# nfc-epd-eink.net
KiCad netlist of a schematic drawn in Altium Designer
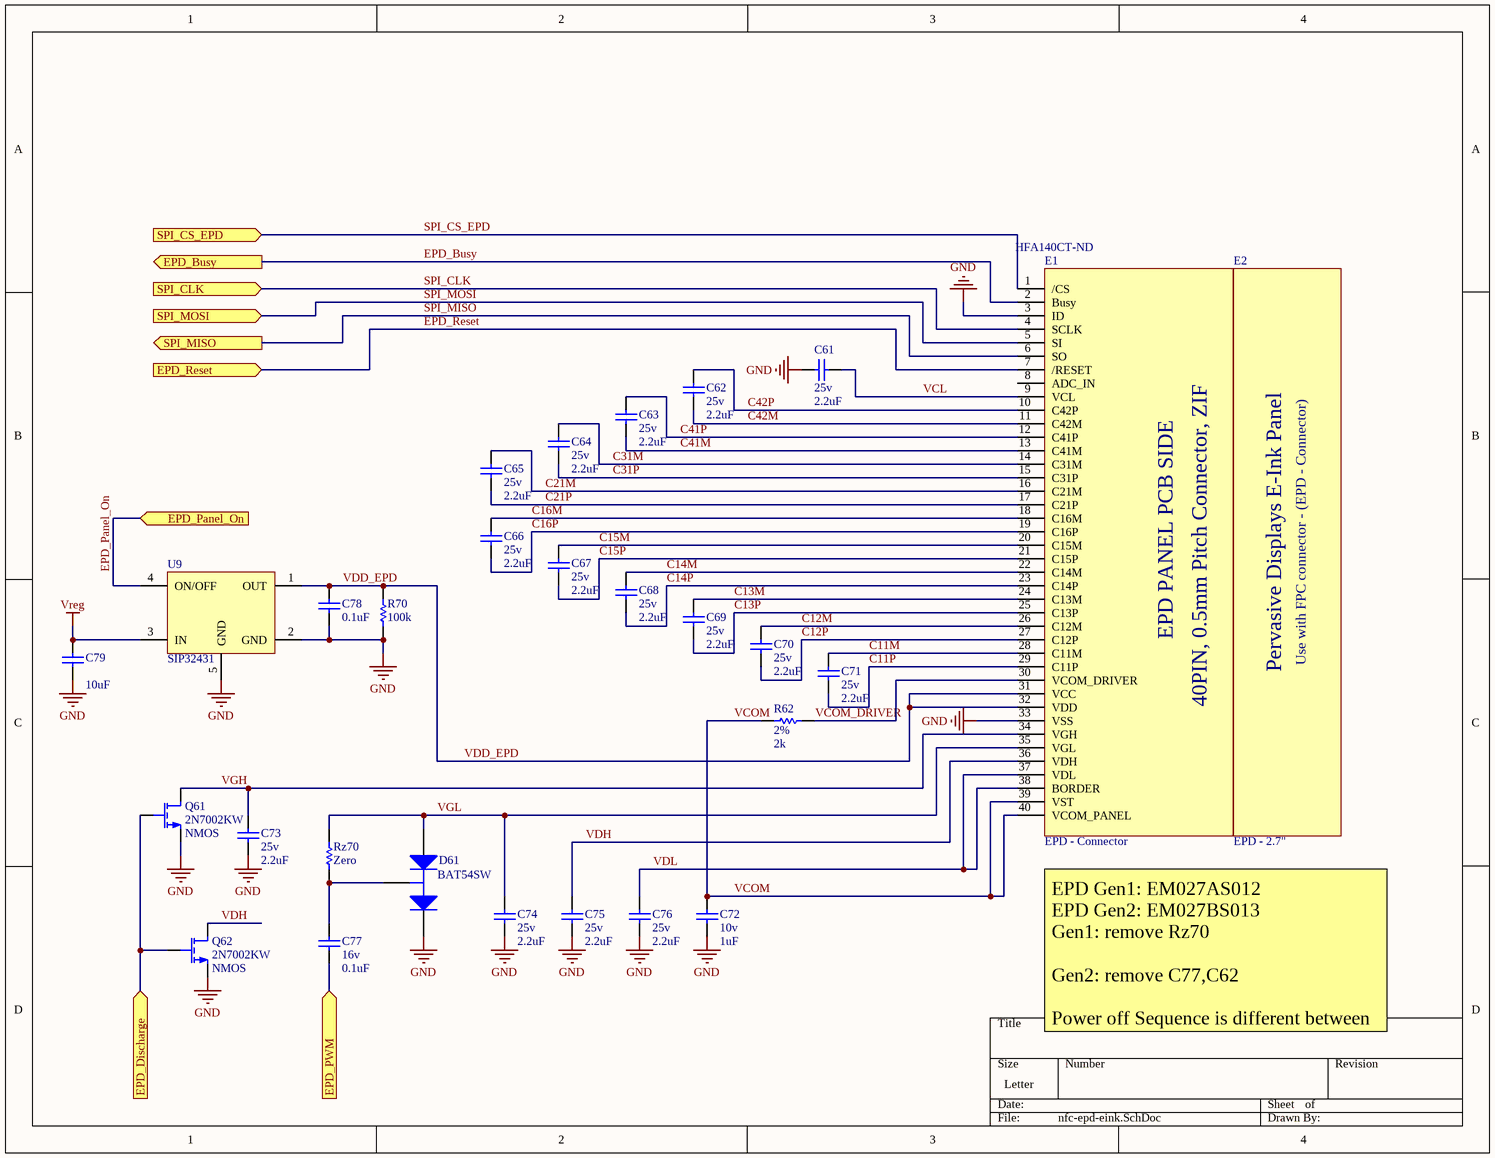
[diagram p0: nfc-epd-eink.SchDoc]

(export (version "E")
  (design (tool "Eeschema 10.0.6"))
  (components
    (comp (ref "C61")
      (value "2.2uF")
      (footprint "0402")
      (description "Ceramic Capacitor (Surface Mount)")
      (fields
        (field (name "MANUFACTURER") "Generic Ceramic Chip Cap (TBD)")
        (field (name "RATING") "25v")
        (field (name "Comment") "Cap")
      )
      (libsource (lib "WISP_AD10") (part "Cap"))
    )
    (comp (ref "C62")
      (value "2.2uF")
      (footprint "0402")
      (description "Ceramic Capacitor (Surface Mount)")
      (fields
        (field (name "MANUFACTURER") "Generic Ceramic Chip Cap (TBD)")
        (field (name "RATING") "25v")
        (field (name "Comment") "Cap")
      )
      (libsource (lib "WISP_AD10") (part "Cap"))
    )
    (comp (ref "C63")
      (value "2.2uF")
      (footprint "0402")
      (description "Ceramic Capacitor (Surface Mount)")
      (fields
        (field (name "MANUFACTURER") "Generic Ceramic Chip Cap (TBD)")
        (field (name "RATING") "25v")
        (field (name "Comment") "Cap")
      )
      (libsource (lib "WISP_AD10") (part "Cap"))
    )
    (comp (ref "C64")
      (value "2.2uF")
      (footprint "0402")
      (description "Ceramic Capacitor (Surface Mount)")
      (fields
        (field (name "MANUFACTURER") "Generic Ceramic Chip Cap (TBD)")
        (field (name "RATING") "25v")
        (field (name "Comment") "Cap")
      )
      (libsource (lib "WISP_AD10") (part "Cap"))
    )
    (comp (ref "C65")
      (value "2.2uF")
      (footprint "0402")
      (description "Ceramic Capacitor (Surface Mount)")
      (fields
        (field (name "MANUFACTURER") "Generic Ceramic Chip Cap (TBD)")
        (field (name "RATING") "25v")
        (field (name "Comment") "Cap")
      )
      (libsource (lib "WISP_AD10") (part "Cap"))
    )
    (comp (ref "C66")
      (value "2.2uF")
      (footprint "0402")
      (description "Ceramic Capacitor (Surface Mount)")
      (fields
        (field (name "MANUFACTURER") "Generic Ceramic Chip Cap (TBD)")
        (field (name "RATING") "25v")
        (field (name "Comment") "Cap")
      )
      (libsource (lib "WISP_AD10") (part "Cap"))
    )
    (comp (ref "C67")
      (value "2.2uF")
      (footprint "0402")
      (description "Ceramic Capacitor (Surface Mount)")
      (fields
        (field (name "MANUFACTURER") "Generic Ceramic Chip Cap (TBD)")
        (field (name "RATING") "25v")
        (field (name "Comment") "Cap")
      )
      (libsource (lib "WISP_AD10") (part "Cap"))
    )
    (comp (ref "C68")
      (value "2.2uF")
      (footprint "0402")
      (description "Ceramic Capacitor (Surface Mount)")
      (fields
        (field (name "MANUFACTURER") "Generic Ceramic Chip Cap (TBD)")
        (field (name "RATING") "25v")
        (field (name "Comment") "Cap")
      )
      (libsource (lib "WISP_AD10") (part "Cap"))
    )
    (comp (ref "C69")
      (value "2.2uF")
      (footprint "0402")
      (description "Ceramic Capacitor (Surface Mount)")
      (fields
        (field (name "MANUFACTURER") "Generic Ceramic Chip Cap (TBD)")
        (field (name "RATING") "25v")
        (field (name "Comment") "Cap")
      )
      (libsource (lib "WISP_AD10") (part "Cap"))
    )
    (comp (ref "C70")
      (value "2.2uF")
      (footprint "0402")
      (description "Ceramic Capacitor (Surface Mount)")
      (fields
        (field (name "MANUFACTURER") "Generic Ceramic Chip Cap (TBD)")
        (field (name "RATING") "25v")
        (field (name "Comment") "Cap")
      )
      (libsource (lib "WISP_AD10") (part "Cap"))
    )
    (comp (ref "C71")
      (value "2.2uF")
      (footprint "0402")
      (description "Ceramic Capacitor (Surface Mount)")
      (fields
        (field (name "MANUFACTURER") "Generic Ceramic Chip Cap (TBD)")
        (field (name "RATING") "25v")
        (field (name "Comment") "Cap")
      )
      (libsource (lib "WISP_AD10") (part "Cap"))
    )
    (comp (ref "C72")
      (value "1uF")
      (footprint "0603")
      (description "Ceramic Capacitor (Surface Mount)")
      (fields
        (field (name "MANUFACTURER") "Generic Ceramic Chip Cap (TBD)")
        (field (name "RATING") "10v")
        (field (name "Comment") "Cap")
      )
      (libsource (lib "WISP_AD10") (part "Cap"))
    )
    (comp (ref "C73")
      (value "2.2uF")
      (footprint "0603")
      (description "Ceramic Capacitor (Surface Mount)")
      (fields
        (field (name "MANUFACTURER") "Generic Ceramic Chip Cap (TBD)")
        (field (name "RATING") "25v")
        (field (name "Comment") "Cap")
      )
      (libsource (lib "WISP_AD10") (part "Cap"))
    )
    (comp (ref "C74")
      (value "2.2uF")
      (footprint "0603")
      (description "Ceramic Capacitor (Surface Mount)")
      (fields
        (field (name "MANUFACTURER") "Generic Ceramic Chip Cap (TBD)")
        (field (name "RATING") "25v")
        (field (name "Comment") "Cap")
      )
      (libsource (lib "WISP_AD10") (part "Cap"))
    )
    (comp (ref "C75")
      (value "2.2uF")
      (footprint "0603")
      (description "Ceramic Capacitor (Surface Mount)")
      (fields
        (field (name "MANUFACTURER") "Generic Ceramic Chip Cap (TBD)")
        (field (name "RATING") "25v")
        (field (name "Comment") "Cap")
      )
      (libsource (lib "WISP_AD10") (part "Cap"))
    )
    (comp (ref "C76")
      (value "2.2uF")
      (footprint "0603")
      (description "Ceramic Capacitor (Surface Mount)")
      (fields
        (field (name "MANUFACTURER") "Generic Ceramic Chip Cap (TBD)")
        (field (name "RATING") "25v")
        (field (name "Comment") "Cap")
      )
      (libsource (lib "WISP_AD10") (part "Cap"))
    )
    (comp (ref "C77")
      (value "0.1uF")
      (footprint "0603")
      (description "Ceramic Capacitor (Surface Mount)")
      (fields
        (field (name "MANUFACTURER") "Generic Ceramic Chip Cap (TBD)")
        (field (name "RATING") "16v")
        (field (name "Comment") "Cap")
      )
      (libsource (lib "WISP_AD10") (part "Cap"))
    )
    (comp (ref "C78")
      (value "0.1uF")
      (footprint "0603")
      (description "Ceramic Capacitor (Surface Mount)")
      (fields (field (name "MANUFACTURER") "Generic Ceramic Chip Cap (TBD)") (field (name "Comment") "Cap"))
      (libsource (lib "WISP_AD10") (part "Cap"))
    )
    (comp (ref "C79")
      (value "10uF")
      (footprint "0603")
      (description "Ceramic Capacitor (Surface Mount)")
      (fields (field (name "MANUFACTURER") "Generic Ceramic Chip Cap (TBD)") (field (name "Comment") "Cap"))
      (libsource (lib "WISP_AD10") (part "Cap"))
    )
    (comp (ref "D61")
      (value "BAT54SW")
      (footprint "SOT-323 / SC-70")
      (description "Diode Array, Two in Series, Small Package SOT-323")
      (fields
        (field (name "MANUFACTURER") "ON Semiconductor")
        (field (name "MANUFACTURER PART NUMBER") "BAT54SWT1G")
      )
      (libsource (lib "WISP_AD10") (part "Diode - Array_1"))
    )
    (comp (ref "E1")
      (value "EPD - Connector")
      (footprint "EPD - Connector")
      (description "FPC, 40pin, 0.5mm Pitch - ZIF")
      (fields
        (field (name "MANUFACTURER") "Hirose Electric Co Ltd")
        (field (name "MANUFACTURER PART NUMBER") "FH12-40S-0.5SH or FH12S-40S-0.5SH")
        (field (name "SUPPLIER PART NUMBER 1") "HFA140CT-ND")
      )
      (libsource (lib "WISP_AD10") (part "EPD - Connector"))
    )
    (comp (ref "E2")
      (value "EPD - 2.7\"")
      (footprint "EPD - EM027AS012")
      (description "2.7\" TFT EPD Panel, STARCONN 089H40 variant")
      (fields
        (field (name "DIGI-KEY PART NUMBER") "EA-LCD-009-ND (should find another supplyer)")
        (field (name "MANUFACTURER") "PERVASIVE DISPLAYS, INC")
      )
      (libsource (lib "WISP_AD10") (part "EPD - Display EM027AS012"))
    )
    (comp (ref "Q61")
      (value "2N7002KW")
      (footprint "SOT-323 / SC-70")
      (description "N-Channel MOSFET")
      (fields
        (field (name "DIGI-KEY PART NUMBER") "2N7002KWCT-ND")
        (field (name "MANUFACTURER") "Fairchild Semiconductor")
        (field (name "ALTIUM_VALUE") "NMOS")
      )
      (libsource (lib "WISP_AD10") (part "MOSFET-N"))
    )
    (comp (ref "Q62")
      (value "2N7002KW")
      (footprint "SOT-323 / SC-70")
      (description "N-Channel MOSFET")
      (fields
        (field (name "DIGI-KEY PART NUMBER") "2N7002KWCT-ND")
        (field (name "MANUFACTURER") "Fairchild Semiconductor")
        (field (name "ALTIUM_VALUE") "NMOS")
      )
      (libsource (lib "WISP_AD10") (part "MOSFET-N"))
    )
    (comp (ref "R62")
      (value "2k")
      (footprint "0603")
      (description "Chip Resistor (Surface Mount)")
      (fields
        (field (name "MANUFACTURER") "Generic Chip Res (TBD)")
        (field (name "RATING") "2%")
        (field (name "Comment") "Res")
      )
      (libsource (lib "WISP_AD10") (part "Res"))
    )
    (comp (ref "R70")
      (value "100k")
      (footprint "0603")
      (description "Chip Resistor (Surface Mount)")
      (fields (field (name "MANUFACTURER") "Generic Chip Res (TBD)") (field (name "Comment") "Res"))
      (libsource (lib "WISP_AD10") (part "Res"))
    )
    (comp (ref "Rz70")
      (value "Zero")
      (footprint "0603")
      (description "Chip Resistor (Surface Mount)")
      (fields
        (field (name "MANUFACTURER") "Generic Chip Res (TBD)")
        (field (name "MANUFACTURER PART NUMBER") "RC0603FR-070RL")
      )
      (libsource (lib "WREL_AD10") (part "Res"))
    )
    (comp (ref "U9")
      (value "SIP32431")
      (footprint "TDFN-4")
      (description "High Sside Switch - 4TDFN package")
      (fields
        (field (name "DIGI-KEY PART NUMBER") "SIP32431DNP3-T1GE4CT-ND")
        (field (name "MANUFACTURER") "Vishay Siliconix")
      )
      (libsource (lib "WISP_AD10") (part "SIP32431"))
    )
  )
  (nets
    (net (code "1") (name "/C11M") (class "Default")
      (node (ref "C71") (pin "2") (pinfunction "2_2") (pintype "passive"))
      (node (ref "E1") (pin "28") (pinfunction "C11M_28") (pintype "passive"))
    )
    (net (code "2") (name "/C11P") (class "Default")
      (node (ref "C71") (pin "1") (pinfunction "1_1") (pintype "passive"))
      (node (ref "E1") (pin "29") (pinfunction "C11P_29") (pintype "passive"))
    )
    (net (code "3") (name "/C12M") (class "Default")
      (node (ref "C70") (pin "1") (pinfunction "1_1") (pintype "passive"))
      (node (ref "E1") (pin "26") (pinfunction "C12M_26") (pintype "passive"))
    )
    (net (code "4") (name "/C12P") (class "Default")
      (node (ref "C70") (pin "2") (pinfunction "2_2") (pintype "passive"))
      (node (ref "E1") (pin "27") (pinfunction "C12P_27") (pintype "passive"))
    )
    (net (code "5") (name "/C13M") (class "Default")
      (node (ref "C69") (pin "2") (pinfunction "2_2") (pintype "passive"))
      (node (ref "E1") (pin "24") (pinfunction "C13M_24") (pintype "passive"))
    )
    (net (code "6") (name "/C13P") (class "Default")
      (node (ref "C69") (pin "1") (pinfunction "1_1") (pintype "passive"))
      (node (ref "E1") (pin "25") (pinfunction "C13P_25") (pintype "passive"))
    )
    (net (code "7") (name "/C14M") (class "Default")
      (node (ref "C68") (pin "2") (pinfunction "2_2") (pintype "passive"))
      (node (ref "E1") (pin "22") (pinfunction "C14M_22") (pintype "passive"))
    )
    (net (code "8") (name "/C14P") (class "Default")
      (node (ref "C68") (pin "1") (pinfunction "1_1") (pintype "passive"))
      (node (ref "E1") (pin "23") (pinfunction "C14P_23") (pintype "passive"))
    )
    (net (code "9") (name "/C15M") (class "Default")
      (node (ref "C67") (pin "2") (pinfunction "2_2") (pintype "passive"))
      (node (ref "E1") (pin "20") (pinfunction "C15M_20") (pintype "passive"))
    )
    (net (code "10") (name "/C15P") (class "Default")
      (node (ref "C67") (pin "1") (pinfunction "1_1") (pintype "passive"))
      (node (ref "E1") (pin "21") (pinfunction "C15P_21") (pintype "passive"))
    )
    (net (code "11") (name "/C16M") (class "Default")
      (node (ref "C66") (pin "2") (pinfunction "2_2") (pintype "passive"))
      (node (ref "E1") (pin "18") (pinfunction "C16M_18") (pintype "passive"))
    )
    (net (code "12") (name "/C16P") (class "Default")
      (node (ref "C66") (pin "1") (pinfunction "1_1") (pintype "passive"))
      (node (ref "E1") (pin "19") (pinfunction "C16P_19") (pintype "passive"))
    )
    (net (code "13") (name "/C21M") (class "Default")
      (node (ref "C65") (pin "2") (pinfunction "2_2") (pintype "passive"))
      (node (ref "E1") (pin "16") (pinfunction "C21M_16") (pintype "passive"))
    )
    (net (code "14") (name "/C21P") (class "Default")
      (node (ref "C65") (pin "1") (pinfunction "1_1") (pintype "passive"))
      (node (ref "E1") (pin "17") (pinfunction "C21P_17") (pintype "passive"))
    )
    (net (code "15") (name "/C31M") (class "Default")
      (node (ref "C64") (pin "2") (pinfunction "2_2") (pintype "passive"))
      (node (ref "E1") (pin "14") (pinfunction "C31M_14") (pintype "passive"))
    )
    (net (code "16") (name "/C31P") (class "Default")
      (node (ref "C64") (pin "1") (pinfunction "1_1") (pintype "passive"))
      (node (ref "E1") (pin "15") (pinfunction "C31P_15") (pintype "passive"))
    )
    (net (code "17") (name "/C41M") (class "Default")
      (node (ref "C63") (pin "1") (pinfunction "1_1") (pintype "passive"))
      (node (ref "E1") (pin "13") (pinfunction "C41M_13") (pintype "passive"))
    )
    (net (code "18") (name "/C41P") (class "Default")
      (node (ref "C63") (pin "2") (pinfunction "2_2") (pintype "passive"))
      (node (ref "E1") (pin "12") (pinfunction "C41P_12") (pintype "passive"))
    )
    (net (code "19") (name "/C42M") (class "Default")
      (node (ref "C62") (pin "2") (pinfunction "2_2") (pintype "passive"))
      (node (ref "E1") (pin "11") (pinfunction "C42M_11") (pintype "passive"))
    )
    (net (code "20") (name "/C42P") (class "Default")
      (node (ref "C62") (pin "1") (pinfunction "1_1") (pintype "passive"))
      (node (ref "E1") (pin "10") (pinfunction "C42P_10") (pintype "passive"))
    )
    (net (code "21") (name "/EPD_Busy") (class "Default")
      (node (ref "E1") (pin "2") (pinfunction "Busy_2") (pintype "passive"))
    )
    (net (code "22") (name "/EPD_Discharge") (class "Default")
      (node (ref "Q61") (pin "1") (pinfunction "G_1") (pintype "passive"))
      (node (ref "Q62") (pin "1") (pinfunction "G_1") (pintype "passive"))
    )
    (net (code "23") (name "/EPD_PWM") (class "Default")
      (node (ref "C77") (pin "1") (pinfunction "1_1") (pintype "passive"))
    )
    (net (code "24") (name "/EPD_Panel_On") (class "Default")
      (node (ref "U9") (pin "4") (pinfunction "ON/OFF_4") (pintype "passive"))
    )
    (net (code "25") (name "/EPD_Reset") (class "Default")
      (node (ref "E1") (pin "7") (pinfunction "/RESET_7") (pintype "passive"))
    )
    (net (code "26") (name "/SPI_CLK") (class "Default")
      (node (ref "E1") (pin "4") (pinfunction "SCLK_4") (pintype "passive"))
    )
    (net (code "27") (name "/SPI_CS_EPD") (class "Default")
      (node (ref "E1") (pin "1") (pinfunction "/CS_1") (pintype "passive"))
    )
    (net (code "28") (name "/SPI_MISO") (class "Default")
      (node (ref "E1") (pin "6") (pinfunction "SO_6") (pintype "passive"))
    )
    (net (code "29") (name "/SPI_MOSI") (class "Default")
      (node (ref "E1") (pin "5") (pinfunction "SI_5") (pintype "passive"))
    )
    (net (code "30") (name "/VCL") (class "Default")
      (node (ref "C61") (pin "1") (pinfunction "1_1") (pintype "passive"))
      (node (ref "E1") (pin "9") (pinfunction "VCL_9") (pintype "passive"))
    )
    (net (code "31") (name "/VCOM") (class "Default")
      (node (ref "C72") (pin "2") (pinfunction "2_2") (pintype "passive"))
      (node (ref "E1") (pin "39") (pinfunction "VST_39") (pintype "passive"))
      (node (ref "E1") (pin "40") (pinfunction "VCOM_PANEL_40") (pintype "passive"))
      (node (ref "R62") (pin "2") (pinfunction "2_2") (pintype "passive"))
    )
    (net (code "32") (name "/VCOM_DRIVER") (class "Default")
      (node (ref "E1") (pin "30") (pinfunction "VCOM_DRIVER_30") (pintype "passive"))
      (node (ref "R62") (pin "1") (pinfunction "1_1") (pintype "passive"))
    )
    (net (code "33") (name "/VDD_EPD") (class "Default")
      (node (ref "C78") (pin "2") (pinfunction "2_2") (pintype "passive"))
      (node (ref "E1") (pin "31") (pinfunction "VCC_31") (pintype "passive"))
      (node (ref "E1") (pin "32") (pinfunction "VDD_32") (pintype "passive"))
      (node (ref "R70") (pin "2") (pinfunction "2_2") (pintype "passive"))
      (node (ref "U9") (pin "1") (pinfunction "OUT_1") (pintype "passive"))
    )
    (net (code "34") (name "/VDH") (class "Default")
      (node (ref "C75") (pin "2") (pinfunction "2_2") (pintype "passive"))
      (node (ref "E1") (pin "36") (pinfunction "VDH_36") (pintype "passive"))
      (node (ref "Q62") (pin "3") (pinfunction "D_3") (pintype "passive"))
    )
    (net (code "35") (name "/VDL") (class "Default")
      (node (ref "C76") (pin "2") (pinfunction "2_2") (pintype "passive"))
      (node (ref "E1") (pin "37") (pinfunction "VDL_37") (pintype "passive"))
      (node (ref "E1") (pin "38") (pinfunction "BORDER_38") (pintype "passive"))
    )
    (net (code "36") (name "/VGH") (class "Default")
      (node (ref "C73") (pin "2") (pinfunction "2_2") (pintype "passive"))
      (node (ref "E1") (pin "34") (pinfunction "VGH_34") (pintype "passive"))
      (node (ref "Q61") (pin "3") (pinfunction "D_3") (pintype "passive"))
    )
    (net (code "37") (name "/VGL") (class "Default")
      (node (ref "C74") (pin "2") (pinfunction "2_2") (pintype "passive"))
      (node (ref "D61") (pin "1") (pinfunction "A_1") (pintype "passive"))
      (node (ref "E1") (pin "35") (pinfunction "VGL_35") (pintype "passive"))
      (node (ref "Rz70") (pin "1") (pinfunction "1_1") (pintype "passive"))
    )
    (net (code "38") (name "GND") (class "Default")
      (node (ref "C61") (pin "2") (pinfunction "2_2") (pintype "passive"))
      (node (ref "C72") (pin "1") (pinfunction "1_1") (pintype "passive"))
      (node (ref "C73") (pin "1") (pinfunction "1_1") (pintype "passive"))
      (node (ref "C74") (pin "1") (pinfunction "1_1") (pintype "passive"))
      (node (ref "C75") (pin "1") (pinfunction "1_1") (pintype "passive"))
      (node (ref "C76") (pin "1") (pinfunction "1_1") (pintype "passive"))
      (node (ref "C78") (pin "1") (pinfunction "1_1") (pintype "passive"))
      (node (ref "C79") (pin "1") (pinfunction "1_1") (pintype "passive"))
      (node (ref "D61") (pin "2") (pinfunction "K_2") (pintype "passive"))
      (node (ref "E1") (pin "3") (pinfunction "ID_3") (pintype "passive"))
      (node (ref "E1") (pin "33") (pinfunction "VSS_33") (pintype "passive"))
      (node (ref "Q61") (pin "2") (pinfunction "S_2") (pintype "passive"))
      (node (ref "Q62") (pin "2") (pinfunction "S_2") (pintype "passive"))
      (node (ref "R70") (pin "1") (pinfunction "1_1") (pintype "passive"))
      (node (ref "U9") (pin "2") (pinfunction "GND_2") (pintype "passive"))
      (node (ref "U9") (pin "5") (pinfunction "GND_5") (pintype "passive"))
    )
    (net (code "39") (name "Net-(D61-C)") (class "Default")
      (node (ref "C77") (pin "2") (pinfunction "2_2") (pintype "passive"))
      (node (ref "D61") (pin "3") (pinfunction "C_3") (pintype "passive"))
      (node (ref "Rz70") (pin "2") (pinfunction "2_2") (pintype "passive"))
    )
    (net (code "40") (name "Vreg") (class "Default")
      (node (ref "C79") (pin "2") (pinfunction "2_2") (pintype "passive"))
      (node (ref "U9") (pin "3") (pinfunction "IN_3") (pintype "passive"))
    )
    (net (code "41") (name "unconnected-(E1-ADC_IN-Pad8)") (class "Default")
      (node (ref "E1") (pin "8") (pinfunction "ADC_IN_8") (pintype "passive"))
    )
  )
)
